# pov.net
KiCad netlist of a schematic drawn in EAGLE
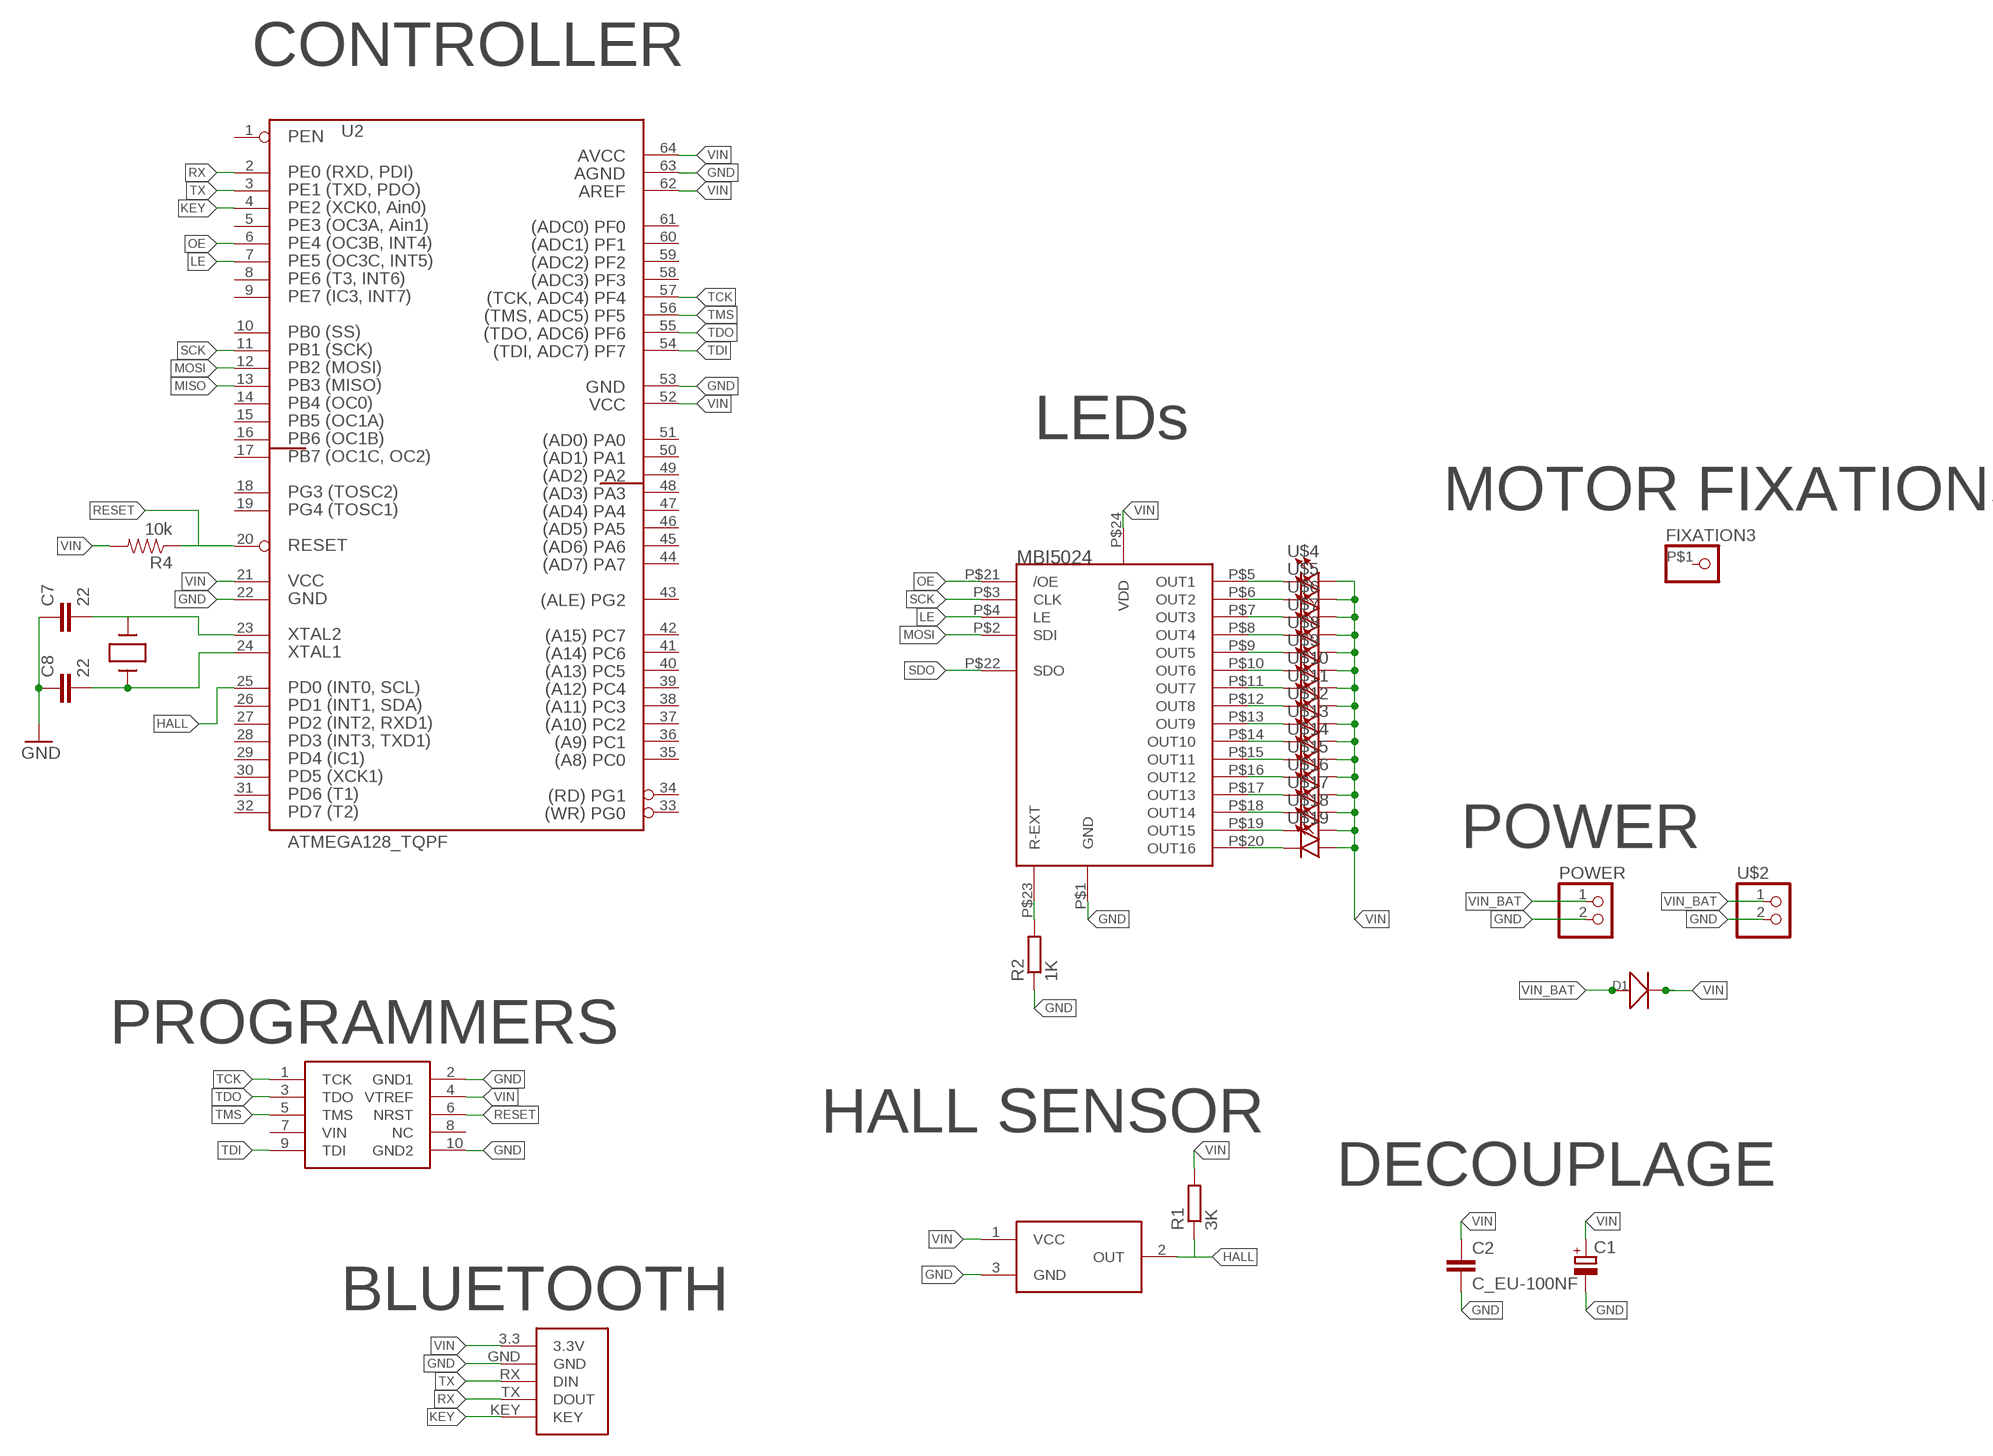
[diagram p0: schematic, sheet 1]

(export (version "E")
  (design (tool "Eeschema 10.0.6"))
  (components
    (comp (ref "C1")
      (value "CPOL_EU-680UF_25V")
      (footprint "eagle-import:E3,5-8")
      (libsource (lib "eagle-import") (part "CPOL_EU-680UF_25V"))
    )
    (comp (ref "C2")
      (value "C_EU-100NF")
      (footprint "eagle-import:C0805")
      (libsource (lib "eagle-import") (part "C_EU-100NF"))
    )
    (comp (ref "C7")
      (value "22")
      (footprint "eagle-import:C0603")
      (libsource (lib "eagle-import") (part "C_EU_22PF"))
    )
    (comp (ref "C8")
      (value "22")
      (footprint "eagle-import:C0603")
      (libsource (lib "eagle-import") (part "C_EU_22PF"))
    )
    (comp (ref "D1")
      (value "D-SOD-123")
      (footprint "eagle-import:SOD123")
      (libsource (lib "eagle-import") (part "D-SOD-123"))
    )
    (comp (ref "FIXATION3")
      (value "CONNEC_1X01SHAFT")
      (footprint "eagle-import:SHAFT2")
      (libsource (lib "eagle-import") (part "CONNEC_1X01SHAFT"))
    )
    (comp (ref "JTAG")
      (value "AVR_JTAG")
      (footprint "eagle-import:AVR_JTAG")
      (libsource (lib "eagle-import") (part "AVR_JTAG"))
    )
    (comp (ref "POWER")
      (value "CONNEC_1X02BASIC")
      (footprint "eagle-import:CONNEC_1X02")
      (libsource (lib "eagle-import") (part "CONNEC_1X02BASIC"))
    )
    (comp (ref "R1")
      (value "3K")
      (footprint "eagle-import:R0805")
      (libsource (lib "eagle-import") (part "RESISTANCE-R0805"))
    )
    (comp (ref "R2")
      (value "1K")
      (footprint "eagle-import:R0805")
      (libsource (lib "eagle-import") (part "RESISTANCE-R0805"))
    )
    (comp (ref "R4")
      (value "10k")
      (footprint "eagle-import:0805")
      (libsource (lib "eagle-import") (part "RESISTOR0805-RES"))
    )
    (comp (ref "U$1")
      (value "DRV5023FAEDBZRQ1")
      (footprint "eagle-import:SOT-23")
      (libsource (lib "eagle-import") (part "DRV5023FAEDBZRQ1"))
    )
    (comp (ref "U$2")
      (value "CONNEC_1X02")
      (footprint "eagle-import:JST_GH_2P")
      (libsource (lib "eagle-import") (part "CONNEC_1X02"))
    )
    (comp (ref "U$4")
      (value "LED1206")
      (footprint "eagle-import:LED-1206")
      (libsource (lib "eagle-import") (part "LED1206"))
    )
    (comp (ref "U$5")
      (value "LED1206")
      (footprint "eagle-import:LED-1206")
      (libsource (lib "eagle-import") (part "LED1206"))
    )
    (comp (ref "U$6")
      (value "LED1206")
      (footprint "eagle-import:LED-1206")
      (libsource (lib "eagle-import") (part "LED1206"))
    )
    (comp (ref "U$7")
      (value "LED1206")
      (footprint "eagle-import:LED-1206")
      (libsource (lib "eagle-import") (part "LED1206"))
    )
    (comp (ref "U$8")
      (value "LED1206")
      (footprint "eagle-import:LED-1206")
      (libsource (lib "eagle-import") (part "LED1206"))
    )
    (comp (ref "U$9")
      (value "LED1206")
      (footprint "eagle-import:LED-1206")
      (libsource (lib "eagle-import") (part "LED1206"))
    )
    (comp (ref "U$10")
      (value "LED1206")
      (footprint "eagle-import:LED-1206")
      (libsource (lib "eagle-import") (part "LED1206"))
    )
    (comp (ref "U$11")
      (value "LED1206")
      (footprint "eagle-import:LED-1206")
      (libsource (lib "eagle-import") (part "LED1206"))
    )
    (comp (ref "U$12")
      (value "LED1206")
      (footprint "eagle-import:LED-1206")
      (libsource (lib "eagle-import") (part "LED1206"))
    )
    (comp (ref "U$13")
      (value "LED1206")
      (footprint "eagle-import:LED-1206")
      (libsource (lib "eagle-import") (part "LED1206"))
    )
    (comp (ref "U$14")
      (value "LED1206")
      (footprint "eagle-import:LED-1206")
      (libsource (lib "eagle-import") (part "LED1206"))
    )
    (comp (ref "U$15")
      (value "LED1206")
      (footprint "eagle-import:LED-1206")
      (libsource (lib "eagle-import") (part "LED1206"))
    )
    (comp (ref "U$16")
      (value "LED1206")
      (footprint "eagle-import:LED-1206")
      (libsource (lib "eagle-import") (part "LED1206"))
    )
    (comp (ref "U$17")
      (value "LED1206")
      (footprint "eagle-import:LED-1206")
      (libsource (lib "eagle-import") (part "LED1206"))
    )
    (comp (ref "U$18")
      (value "LED1206")
      (footprint "eagle-import:LED-1206")
      (libsource (lib "eagle-import") (part "LED1206"))
    )
    (comp (ref "U$19")
      (value "LED1206")
      (footprint "eagle-import:LED-1206")
      (libsource (lib "eagle-import") (part "LED1206"))
    )
    (comp (ref "U$23")
      (value "HC05")
      (footprint "eagle-import:HC-05")
      (libsource (lib "eagle-import") (part "HC05"))
    )
    (comp (ref "U1")
      (value "MBI5024")
      (footprint "eagle-import:SOP24L-300-1.0")
      (libsource (lib "eagle-import") (part "MBI5024"))
    )
    (comp (ref "U2")
      (value "ATMEGA128_TQPF")
      (footprint "eagle-import:TQFP64")
      (libsource (lib "eagle-import") (part "ATMEGA128_TQPF"))
    )
    (comp (ref "XTAL1")
      (value "QUARTZ")
      (footprint "eagle-import:HC49US")
      (libsource (lib "eagle-import") (part "QUARTZ"))
    )
  )
  (nets
    (net (code "1") (name "GND") (class "Default")
      (node (ref "C1") (pin "-") (pinfunction "-_-") (pintype "passive"))
      (node (ref "C2") (pin "2") (pinfunction "2_2") (pintype "passive"))
      (node (ref "C7") (pin "1") (pinfunction "1_1") (pintype "passive"))
      (node (ref "C8") (pin "1") (pinfunction "1_1") (pintype "passive"))
      (node (ref "JTAG") (pin "10") (pinfunction "GND2_10") (pintype "bidirectional"))
      (node (ref "JTAG") (pin "2") (pinfunction "GND1_2") (pintype "bidirectional"))
      (node (ref "POWER") (pin "2") (pinfunction "2_2") (pintype "passive"))
      (node (ref "R2") (pin "1") (pinfunction "1_1") (pintype "passive"))
      (node (ref "U$1") (pin "3") (pinfunction "GND_3") (pintype "bidirectional"))
      (node (ref "U$2") (pin "2") (pinfunction "2_2") (pintype "passive"))
      (node (ref "U$23") (pin "GND") (pinfunction "GND_GND") (pintype "bidirectional"))
      (node (ref "U1") (pin "P$1") (pinfunction "GND_P$1") (pintype "bidirectional"))
      (node (ref "U2") (pin "22") (pinfunction "22_22") (pintype "power_in"))
      (node (ref "U2") (pin "53") (pinfunction "53_53") (pintype "power_in"))
      (node (ref "U2") (pin "63") (pinfunction "63_63") (pintype "bidirectional"))
    )
    (net (code "2") (name "HALL") (class "Default")
      (node (ref "R1") (pin "1") (pinfunction "1_1") (pintype "passive"))
      (node (ref "U$1") (pin "2") (pinfunction "OUT_2") (pintype "bidirectional"))
      (node (ref "U2") (pin "25") (pinfunction "25_25") (pintype "bidirectional"))
    )
    (net (code "3") (name "KEY") (class "Default")
      (node (ref "U$23") (pin "KEY") (pinfunction "KEY_KEY") (pintype "bidirectional"))
      (node (ref "U2") (pin "4") (pinfunction "4_4") (pintype "bidirectional"))
    )
    (net (code "4") (name "LE") (class "Default")
      (node (ref "U1") (pin "P$4") (pinfunction "LE_P$4") (pintype "bidirectional"))
      (node (ref "U2") (pin "7") (pinfunction "7_7") (pintype "bidirectional"))
    )
    (net (code "5") (name "MISO") (class "Default")
      (node (ref "U2") (pin "13") (pinfunction "13_13") (pintype "bidirectional"))
    )
    (net (code "6") (name "MOSI") (class "Default")
      (node (ref "U1") (pin "P$2") (pinfunction "SDI_P$2") (pintype "bidirectional"))
      (node (ref "U2") (pin "12") (pinfunction "12_12") (pintype "bidirectional"))
    )
    (net (code "7") (name "Net-(C7-Pad2)") (class "Default")
      (node (ref "C7") (pin "2") (pinfunction "2_2") (pintype "passive"))
      (node (ref "U2") (pin "23") (pinfunction "23_23") (pintype "bidirectional"))
      (node (ref "XTAL1") (pin "2") (pinfunction "2_2") (pintype "bidirectional"))
    )
    (net (code "8") (name "Net-(C8-Pad2)") (class "Default")
      (node (ref "C8") (pin "2") (pinfunction "2_2") (pintype "passive"))
      (node (ref "U2") (pin "24") (pinfunction "24_24") (pintype "bidirectional"))
      (node (ref "XTAL1") (pin "1") (pinfunction "1_1") (pintype "bidirectional"))
    )
    (net (code "9") (name "Net-(U1-OUT1)") (class "Default")
      (node (ref "U$4") (pin "C") (pinfunction "C_C") (pintype "passive"))
      (node (ref "U1") (pin "P$5") (pinfunction "OUT1_P$5") (pintype "bidirectional"))
    )
    (net (code "10") (name "Net-(U1-OUT2)") (class "Default")
      (node (ref "U$5") (pin "C") (pinfunction "C_C") (pintype "passive"))
      (node (ref "U1") (pin "P$6") (pinfunction "OUT2_P$6") (pintype "bidirectional"))
    )
    (net (code "11") (name "Net-(U1-OUT3)") (class "Default")
      (node (ref "U$6") (pin "C") (pinfunction "C_C") (pintype "passive"))
      (node (ref "U1") (pin "P$7") (pinfunction "OUT3_P$7") (pintype "bidirectional"))
    )
    (net (code "12") (name "Net-(U1-OUT4)") (class "Default")
      (node (ref "U$7") (pin "C") (pinfunction "C_C") (pintype "passive"))
      (node (ref "U1") (pin "P$8") (pinfunction "OUT4_P$8") (pintype "bidirectional"))
    )
    (net (code "13") (name "Net-(U1-OUT5)") (class "Default")
      (node (ref "U$8") (pin "C") (pinfunction "C_C") (pintype "passive"))
      (node (ref "U1") (pin "P$9") (pinfunction "OUT5_P$9") (pintype "bidirectional"))
    )
    (net (code "14") (name "Net-(U1-OUT6)") (class "Default")
      (node (ref "U$9") (pin "C") (pinfunction "C_C") (pintype "passive"))
      (node (ref "U1") (pin "P$10") (pinfunction "OUT6_P$10") (pintype "bidirectional"))
    )
    (net (code "15") (name "Net-(U1-OUT7)") (class "Default")
      (node (ref "U$10") (pin "C") (pinfunction "C_C") (pintype "passive"))
      (node (ref "U1") (pin "P$11") (pinfunction "OUT7_P$11") (pintype "bidirectional"))
    )
    (net (code "16") (name "Net-(U1-OUT8)") (class "Default")
      (node (ref "U$11") (pin "C") (pinfunction "C_C") (pintype "passive"))
      (node (ref "U1") (pin "P$12") (pinfunction "OUT8_P$12") (pintype "bidirectional"))
    )
    (net (code "17") (name "Net-(U1-OUT9)") (class "Default")
      (node (ref "U$12") (pin "C") (pinfunction "C_C") (pintype "passive"))
      (node (ref "U1") (pin "P$13") (pinfunction "OUT9_P$13") (pintype "bidirectional"))
    )
    (net (code "18") (name "Net-(U1-OUT10)") (class "Default")
      (node (ref "U$13") (pin "C") (pinfunction "C_C") (pintype "passive"))
      (node (ref "U1") (pin "P$14") (pinfunction "OUT10_P$14") (pintype "bidirectional"))
    )
    (net (code "19") (name "Net-(U1-OUT11)") (class "Default")
      (node (ref "U$14") (pin "C") (pinfunction "C_C") (pintype "passive"))
      (node (ref "U1") (pin "P$15") (pinfunction "OUT11_P$15") (pintype "bidirectional"))
    )
    (net (code "20") (name "Net-(U1-OUT12)") (class "Default")
      (node (ref "U$15") (pin "C") (pinfunction "C_C") (pintype "passive"))
      (node (ref "U1") (pin "P$16") (pinfunction "OUT12_P$16") (pintype "bidirectional"))
    )
    (net (code "21") (name "Net-(U1-OUT13)") (class "Default")
      (node (ref "U$16") (pin "C") (pinfunction "C_C") (pintype "passive"))
      (node (ref "U1") (pin "P$17") (pinfunction "OUT13_P$17") (pintype "bidirectional"))
    )
    (net (code "22") (name "Net-(U1-OUT14)") (class "Default")
      (node (ref "U$17") (pin "C") (pinfunction "C_C") (pintype "passive"))
      (node (ref "U1") (pin "P$18") (pinfunction "OUT14_P$18") (pintype "bidirectional"))
    )
    (net (code "23") (name "Net-(U1-OUT15)") (class "Default")
      (node (ref "U$18") (pin "C") (pinfunction "C_C") (pintype "passive"))
      (node (ref "U1") (pin "P$19") (pinfunction "OUT15_P$19") (pintype "bidirectional"))
    )
    (net (code "24") (name "Net-(U1-OUT16)") (class "Default")
      (node (ref "U$19") (pin "C") (pinfunction "C_C") (pintype "passive"))
      (node (ref "U1") (pin "P$20") (pinfunction "OUT16_P$20") (pintype "bidirectional"))
    )
    (net (code "25") (name "Net-(U1-R-EXT)") (class "Default")
      (node (ref "R2") (pin "2") (pinfunction "2_2") (pintype "passive"))
      (node (ref "U1") (pin "P$23") (pinfunction "R-EXT_P$23") (pintype "bidirectional"))
    )
    (net (code "26") (name "OE") (class "Default")
      (node (ref "U1") (pin "P$21") (pinfunction "/OE_P$21") (pintype "bidirectional"))
      (node (ref "U2") (pin "6") (pinfunction "6_6") (pintype "bidirectional"))
    )
    (net (code "27") (name "RESET") (class "Default")
      (node (ref "JTAG") (pin "6") (pinfunction "NRST_6") (pintype "bidirectional"))
      (node (ref "R4") (pin "1") (pinfunction "1_1") (pintype "passive"))
      (node (ref "U2") (pin "20") (pinfunction "20_20") (pintype "input"))
    )
    (net (code "28") (name "RX") (class "Default")
      (node (ref "U$23") (pin "TX") (pinfunction "DOUT_TX") (pintype "bidirectional"))
      (node (ref "U2") (pin "2") (pinfunction "2_2") (pintype "bidirectional"))
    )
    (net (code "29") (name "SCK") (class "Default")
      (node (ref "U1") (pin "P$3") (pinfunction "CLK_P$3") (pintype "bidirectional"))
      (node (ref "U2") (pin "11") (pinfunction "11_11") (pintype "bidirectional"))
    )
    (net (code "30") (name "SDO") (class "Default")
      (node (ref "U1") (pin "P$22") (pinfunction "SDO_P$22") (pintype "bidirectional"))
    )
    (net (code "31") (name "TCK") (class "Default")
      (node (ref "JTAG") (pin "1") (pinfunction "TCK_1") (pintype "bidirectional"))
      (node (ref "U2") (pin "57") (pinfunction "57_57") (pintype "input"))
    )
    (net (code "32") (name "TDI") (class "Default")
      (node (ref "JTAG") (pin "9") (pinfunction "TDI_9") (pintype "bidirectional"))
      (node (ref "U2") (pin "54") (pinfunction "54_54") (pintype "input"))
    )
    (net (code "33") (name "TDO") (class "Default")
      (node (ref "JTAG") (pin "3") (pinfunction "TDO_3") (pintype "bidirectional"))
      (node (ref "U2") (pin "55") (pinfunction "55_55") (pintype "input"))
    )
    (net (code "34") (name "TMS") (class "Default")
      (node (ref "JTAG") (pin "5") (pinfunction "TMS_5") (pintype "bidirectional"))
      (node (ref "U2") (pin "56") (pinfunction "56_56") (pintype "input"))
    )
    (net (code "35") (name "TX") (class "Default")
      (node (ref "U$23") (pin "RX") (pinfunction "DIN_RX") (pintype "bidirectional"))
      (node (ref "U2") (pin "3") (pinfunction "3_3") (pintype "bidirectional"))
    )
    (net (code "36") (name "VIN") (class "Default")
      (node (ref "C1") (pin "+") (pinfunction "+_+") (pintype "passive"))
      (node (ref "C2") (pin "1") (pinfunction "1_1") (pintype "passive"))
      (node (ref "D1") (pin "-") (pinfunction "-_-") (pintype "passive"))
      (node (ref "JTAG") (pin "4") (pinfunction "VTREF_4") (pintype "bidirectional"))
      (node (ref "R1") (pin "2") (pinfunction "2_2") (pintype "passive"))
      (node (ref "R4") (pin "2") (pinfunction "2_2") (pintype "passive"))
      (node (ref "U$1") (pin "1") (pinfunction "VCC_1") (pintype "bidirectional"))
      (node (ref "U$10") (pin "A") (pinfunction "A_A") (pintype "passive"))
      (node (ref "U$11") (pin "A") (pinfunction "A_A") (pintype "passive"))
      (node (ref "U$12") (pin "A") (pinfunction "A_A") (pintype "passive"))
      (node (ref "U$13") (pin "A") (pinfunction "A_A") (pintype "passive"))
      (node (ref "U$14") (pin "A") (pinfunction "A_A") (pintype "passive"))
      (node (ref "U$15") (pin "A") (pinfunction "A_A") (pintype "passive"))
      (node (ref "U$16") (pin "A") (pinfunction "A_A") (pintype "passive"))
      (node (ref "U$17") (pin "A") (pinfunction "A_A") (pintype "passive"))
      (node (ref "U$18") (pin "A") (pinfunction "A_A") (pintype "passive"))
      (node (ref "U$19") (pin "A") (pinfunction "A_A") (pintype "passive"))
      (node (ref "U$23") (pin "3.3") (pinfunction "3.3V_3.3") (pintype "bidirectional"))
      (node (ref "U$4") (pin "A") (pinfunction "A_A") (pintype "passive"))
      (node (ref "U$5") (pin "A") (pinfunction "A_A") (pintype "passive"))
      (node (ref "U$6") (pin "A") (pinfunction "A_A") (pintype "passive"))
      (node (ref "U$7") (pin "A") (pinfunction "A_A") (pintype "passive"))
      (node (ref "U$8") (pin "A") (pinfunction "A_A") (pintype "passive"))
      (node (ref "U$9") (pin "A") (pinfunction "A_A") (pintype "passive"))
      (node (ref "U1") (pin "P$24") (pinfunction "VDD_P$24") (pintype "bidirectional"))
      (node (ref "U2") (pin "21") (pinfunction "21_21") (pintype "power_in"))
      (node (ref "U2") (pin "52") (pinfunction "52_52") (pintype "power_in"))
      (node (ref "U2") (pin "62") (pinfunction "62_62") (pintype "bidirectional"))
      (node (ref "U2") (pin "64") (pinfunction "64_64") (pintype "bidirectional"))
    )
    (net (code "37") (name "VIN_BAT") (class "Default")
      (node (ref "D1") (pin "+") (pinfunction "+_+") (pintype "passive"))
      (node (ref "POWER") (pin "1") (pinfunction "1_1") (pintype "passive"))
      (node (ref "U$2") (pin "1") (pinfunction "1_1") (pintype "passive"))
    )
    (net (code "38") (name "unconnected-(FIXATION3-1-PadP$1)") (class "Default")
      (node (ref "FIXATION3") (pin "P$1") (pinfunction "1_P$1") (pintype "passive"))
    )
    (net (code "39") (name "unconnected-(JTAG-NC-Pad8)") (class "Default")
      (node (ref "JTAG") (pin "8") (pinfunction "NC_8") (pintype "bidirectional"))
    )
    (net (code "40") (name "unconnected-(JTAG-VIN-Pad7)") (class "Default")
      (node (ref "JTAG") (pin "7") (pinfunction "VIN_7") (pintype "bidirectional"))
    )
    (net (code "41") (name "unconnected-(U2-Pad1)") (class "Default")
      (node (ref "U2") (pin "1") (pinfunction "1_1") (pintype "input"))
    )
    (net (code "42") (name "unconnected-(U2-Pad5)") (class "Default")
      (node (ref "U2") (pin "5") (pinfunction "5_5") (pintype "bidirectional"))
    )
    (net (code "43") (name "unconnected-(U2-Pad8)") (class "Default")
      (node (ref "U2") (pin "8") (pinfunction "8_8") (pintype "bidirectional"))
    )
    (net (code "44") (name "unconnected-(U2-Pad9)") (class "Default")
      (node (ref "U2") (pin "9") (pinfunction "9_9") (pintype "bidirectional"))
    )
    (net (code "45") (name "unconnected-(U2-Pad10)") (class "Default")
      (node (ref "U2") (pin "10") (pinfunction "10_10") (pintype "bidirectional"))
    )
    (net (code "46") (name "unconnected-(U2-Pad14)") (class "Default")
      (node (ref "U2") (pin "14") (pinfunction "14_14") (pintype "bidirectional"))
    )
    (net (code "47") (name "unconnected-(U2-Pad15)") (class "Default")
      (node (ref "U2") (pin "15") (pinfunction "15_15") (pintype "bidirectional"))
    )
    (net (code "48") (name "unconnected-(U2-Pad16)") (class "Default")
      (node (ref "U2") (pin "16") (pinfunction "16_16") (pintype "bidirectional"))
    )
    (net (code "49") (name "unconnected-(U2-Pad17)") (class "Default")
      (node (ref "U2") (pin "17") (pinfunction "17_17") (pintype "bidirectional"))
    )
    (net (code "50") (name "unconnected-(U2-Pad18)") (class "Default")
      (node (ref "U2") (pin "18") (pinfunction "18_18") (pintype "bidirectional"))
    )
    (net (code "51") (name "unconnected-(U2-Pad19)") (class "Default")
      (node (ref "U2") (pin "19") (pinfunction "19_19") (pintype "bidirectional"))
    )
    (net (code "52") (name "unconnected-(U2-Pad26)") (class "Default")
      (node (ref "U2") (pin "26") (pinfunction "26_26") (pintype "bidirectional"))
    )
    (net (code "53") (name "unconnected-(U2-Pad27)") (class "Default")
      (node (ref "U2") (pin "27") (pinfunction "27_27") (pintype "bidirectional"))
    )
    (net (code "54") (name "unconnected-(U2-Pad28)") (class "Default")
      (node (ref "U2") (pin "28") (pinfunction "28_28") (pintype "bidirectional"))
    )
    (net (code "55") (name "unconnected-(U2-Pad29)") (class "Default")
      (node (ref "U2") (pin "29") (pinfunction "29_29") (pintype "bidirectional"))
    )
    (net (code "56") (name "unconnected-(U2-Pad30)") (class "Default")
      (node (ref "U2") (pin "30") (pinfunction "30_30") (pintype "bidirectional"))
    )
    (net (code "57") (name "unconnected-(U2-Pad31)") (class "Default")
      (node (ref "U2") (pin "31") (pinfunction "31_31") (pintype "bidirectional"))
    )
    (net (code "58") (name "unconnected-(U2-Pad32)") (class "Default")
      (node (ref "U2") (pin "32") (pinfunction "32_32") (pintype "bidirectional"))
    )
    (net (code "59") (name "unconnected-(U2-Pad33)") (class "Default")
      (node (ref "U2") (pin "33") (pinfunction "33_33") (pintype "bidirectional"))
    )
    (net (code "60") (name "unconnected-(U2-Pad34)") (class "Default")
      (node (ref "U2") (pin "34") (pinfunction "34_34") (pintype "bidirectional"))
    )
    (net (code "61") (name "unconnected-(U2-Pad35)") (class "Default")
      (node (ref "U2") (pin "35") (pinfunction "35_35") (pintype "output"))
    )
    (net (code "62") (name "unconnected-(U2-Pad36)") (class "Default")
      (node (ref "U2") (pin "36") (pinfunction "36_36") (pintype "output"))
    )
    (net (code "63") (name "unconnected-(U2-Pad37)") (class "Default")
      (node (ref "U2") (pin "37") (pinfunction "37_37") (pintype "output"))
    )
    (net (code "64") (name "unconnected-(U2-Pad38)") (class "Default")
      (node (ref "U2") (pin "38") (pinfunction "38_38") (pintype "output"))
    )
    (net (code "65") (name "unconnected-(U2-Pad39)") (class "Default")
      (node (ref "U2") (pin "39") (pinfunction "39_39") (pintype "output"))
    )
    (net (code "66") (name "unconnected-(U2-Pad40)") (class "Default")
      (node (ref "U2") (pin "40") (pinfunction "40_40") (pintype "output"))
    )
    (net (code "67") (name "unconnected-(U2-Pad41)") (class "Default")
      (node (ref "U2") (pin "41") (pinfunction "41_41") (pintype "output"))
    )
    (net (code "68") (name "unconnected-(U2-Pad42)") (class "Default")
      (node (ref "U2") (pin "42") (pinfunction "42_42") (pintype "output"))
    )
    (net (code "69") (name "unconnected-(U2-Pad43)") (class "Default")
      (node (ref "U2") (pin "43") (pinfunction "43_43") (pintype "bidirectional"))
    )
    (net (code "70") (name "unconnected-(U2-Pad44)") (class "Default")
      (node (ref "U2") (pin "44") (pinfunction "44_44") (pintype "bidirectional"))
    )
    (net (code "71") (name "unconnected-(U2-Pad45)") (class "Default")
      (node (ref "U2") (pin "45") (pinfunction "45_45") (pintype "bidirectional"))
    )
    (net (code "72") (name "unconnected-(U2-Pad46)") (class "Default")
      (node (ref "U2") (pin "46") (pinfunction "46_46") (pintype "bidirectional"))
    )
    (net (code "73") (name "unconnected-(U2-Pad47)") (class "Default")
      (node (ref "U2") (pin "47") (pinfunction "47_47") (pintype "bidirectional"))
    )
    (net (code "74") (name "unconnected-(U2-Pad48)") (class "Default")
      (node (ref "U2") (pin "48") (pinfunction "48_48") (pintype "bidirectional"))
    )
    (net (code "75") (name "unconnected-(U2-Pad49)") (class "Default")
      (node (ref "U2") (pin "49") (pinfunction "49_49") (pintype "bidirectional"))
    )
    (net (code "76") (name "unconnected-(U2-Pad50)") (class "Default")
      (node (ref "U2") (pin "50") (pinfunction "50_50") (pintype "bidirectional"))
    )
    (net (code "77") (name "unconnected-(U2-Pad51)") (class "Default")
      (node (ref "U2") (pin "51") (pinfunction "51_51") (pintype "bidirectional"))
    )
    (net (code "78") (name "unconnected-(U2-Pad58)") (class "Default")
      (node (ref "U2") (pin "58") (pinfunction "58_58") (pintype "input"))
    )
    (net (code "79") (name "unconnected-(U2-Pad59)") (class "Default")
      (node (ref "U2") (pin "59") (pinfunction "59_59") (pintype "input"))
    )
    (net (code "80") (name "unconnected-(U2-Pad60)") (class "Default")
      (node (ref "U2") (pin "60") (pinfunction "60_60") (pintype "input"))
    )
    (net (code "81") (name "unconnected-(U2-Pad61)") (class "Default")
      (node (ref "U2") (pin "61") (pinfunction "61_61") (pintype "input"))
    )
  )
)
